# I-Ching_connection_board_v3_2020-09-12_0.net
KiCad netlist of a schematic drawn in EasyEDA
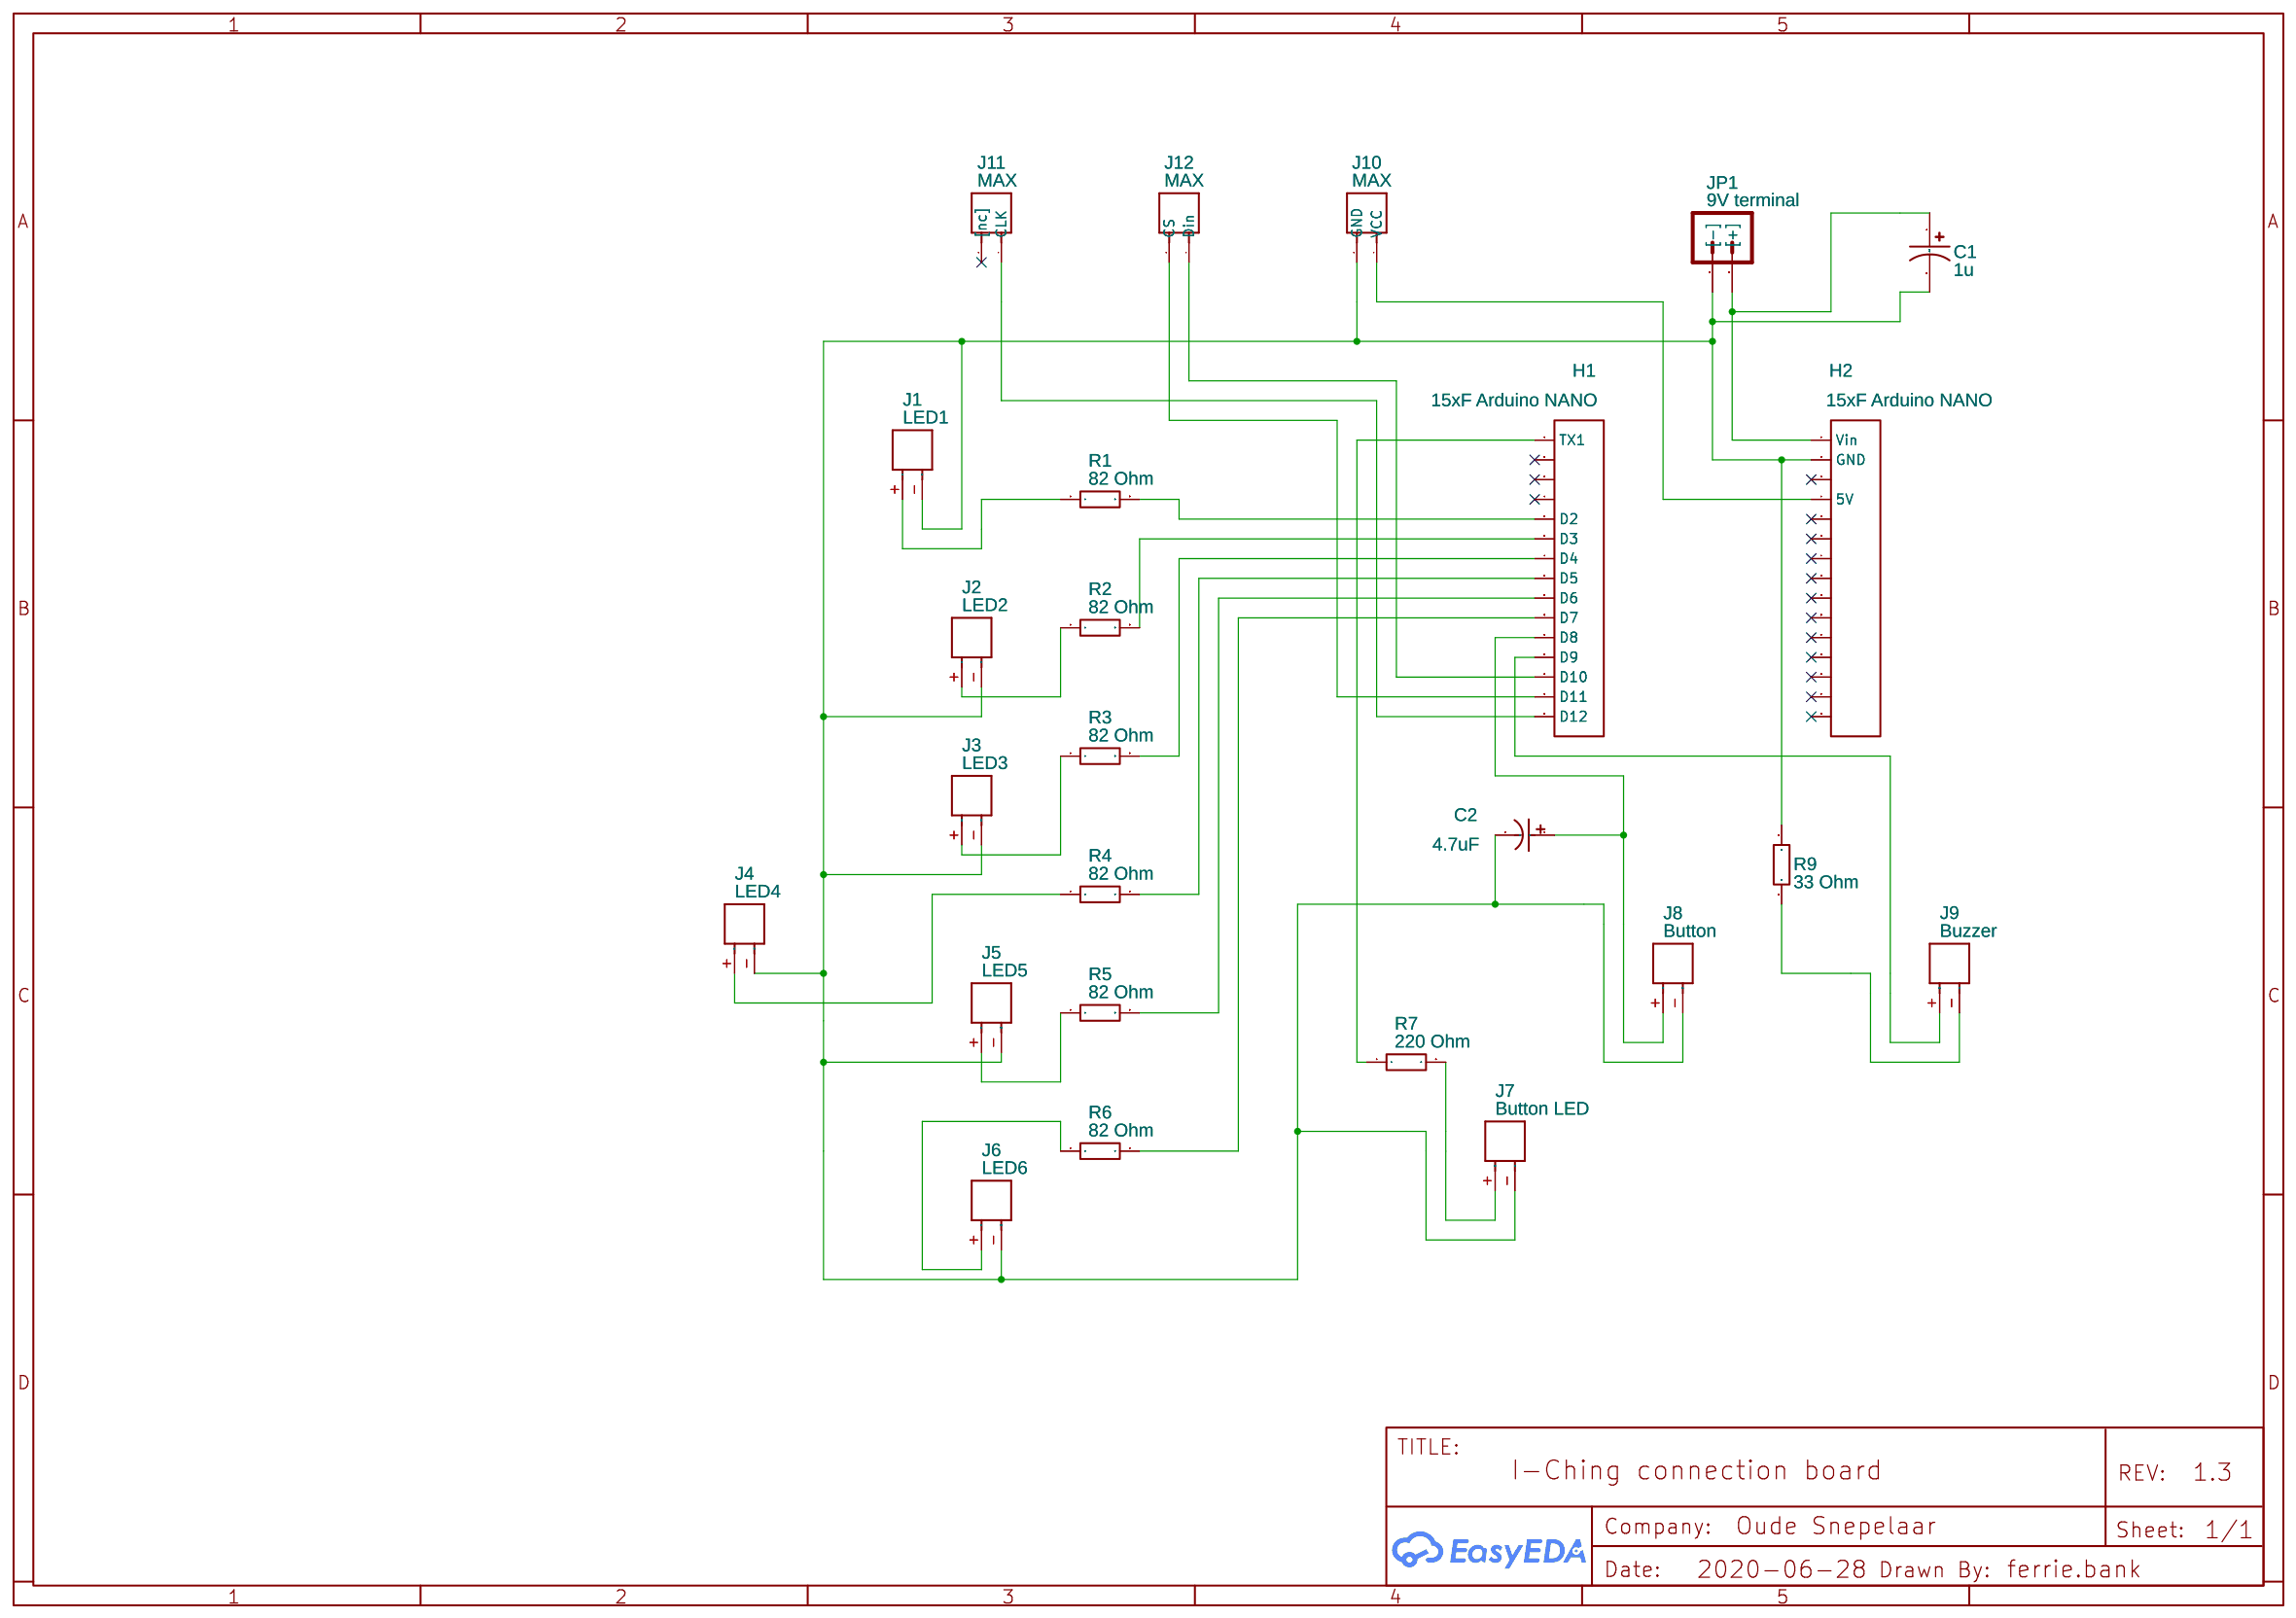
[diagram p0: schematic sheet]

(export (version "E")
  (design (tool "Eeschema 10.0.6"))
  (components
    (comp (ref "C1") (value "1u") (libsource (lib "") (part "CE_TH_D5.0×F2.0_US")))
    (comp (ref "C2")
      (value "4.7uF")
      (fields (field (name "BOM_Manufacturer Part") "0.1UF 50V") (field (name "BOM_Supplier Part") "C28061"))
      (libsource (lib "") (part "0.1UF 50V"))
    )
    (comp (ref "H1")
      (value "15xF Arduino NANO")
      (fields
        (field (name "BOM_Manufacturer Part") "220S-1*15P H=8.5MM Ytype Gold-plated")
        (field (name "BOM_Supplier Part") "C124408")
      )
      (libsource (lib "") (part "Header-Female-2.54_1x15_1"))
    )
    (comp (ref "H2")
      (value "15xF Arduino NANO")
      (fields
        (field (name "BOM_Manufacturer Part") "220S-1*15P H=8.5MM Ytype Gold-plated")
        (field (name "BOM_Supplier Part") "C124408")
      )
      (libsource (lib "") (part "Header-Female-2.54_1x15"))
    )
    (comp (ref "J1")
      (value "LED1")
      (fields (field (name "BOM_Manufacturer Part") "ZB2001-02"))
      (libsource (lib "") (part "ZB2001-02_1"))
    )
    (comp (ref "J2")
      (value "LED2")
      (fields (field (name "BOM_Manufacturer Part") "ZB2001-02"))
      (libsource (lib "") (part "ZB2001-02_1"))
    )
    (comp (ref "J3")
      (value "LED3")
      (fields (field (name "BOM_Manufacturer Part") "ZB2001-02"))
      (libsource (lib "") (part "ZB2001-02_1"))
    )
    (comp (ref "J4")
      (value "LED4")
      (fields (field (name "BOM_Manufacturer Part") "ZB2001-02"))
      (libsource (lib "") (part "ZB2001-02_1"))
    )
    (comp (ref "J5")
      (value "LED5")
      (fields (field (name "BOM_Manufacturer Part") "ZB2001-02"))
      (libsource (lib "") (part "ZB2001-02_1"))
    )
    (comp (ref "J6")
      (value "LED6")
      (fields (field (name "BOM_Manufacturer Part") "ZB2001-02"))
      (libsource (lib "") (part "ZB2001-02_1"))
    )
    (comp (ref "J7")
      (value "Button LED")
      (fields (field (name "BOM_Manufacturer Part") "ZB2001-02"))
      (libsource (lib "") (part "ZB2001-02_1"))
    )
    (comp (ref "J8")
      (value "Button")
      (fields (field (name "BOM_Manufacturer Part") "ZB2001-02"))
      (libsource (lib "") (part "ZB2001-02_1"))
    )
    (comp (ref "J9")
      (value "Buzzer")
      (fields (field (name "BOM_Manufacturer Part") "ZB2001-02"))
      (libsource (lib "") (part "ZB2001-02_1"))
    )
    (comp (ref "J10")
      (value "MAX")
      (fields (field (name "BOM_Manufacturer Part") "ZB2001-02"))
      (libsource (lib "") (part "ZB2001-02_3"))
    )
    (comp (ref "J11")
      (value "MAX")
      (fields (field (name "BOM_Manufacturer Part") "ZB2001-02"))
      (libsource (lib "") (part "ZB2001-02_2"))
    )
    (comp (ref "J12")
      (value "MAX")
      (fields (field (name "BOM_Manufacturer Part") "ZB2001-02"))
      (libsource (lib "") (part "ZB2001-02"))
    )
    (comp (ref "JP1") (value "9V terminal") (libsource (lib "") (part "Screw Terminal 2-Pin (5mm Pitch)")))
    (comp (ref "R1")
      (value "82 Ohm")
      (fields
        (field (name "BOM_Manufacturer Part") "MFR-25FTE52-300K")
        (field (name "BOM_Supplier Part") "C173001")
      )
      (libsource (lib "") (part "MFR-25FTE52-300K"))
    )
    (comp (ref "R2")
      (value "82 Ohm")
      (fields
        (field (name "BOM_Manufacturer Part") "MFR-25FTE52-300K")
        (field (name "BOM_Supplier Part") "C173001")
      )
      (libsource (lib "") (part "MFR-25FTE52-300K"))
    )
    (comp (ref "R3")
      (value "82 Ohm")
      (fields
        (field (name "BOM_Manufacturer Part") "MFR-25FTE52-300K")
        (field (name "BOM_Supplier Part") "C173001")
      )
      (libsource (lib "") (part "MFR-25FTE52-300K"))
    )
    (comp (ref "R4")
      (value "82 Ohm")
      (fields
        (field (name "BOM_Manufacturer Part") "MFR-25FTE52-300K")
        (field (name "BOM_Supplier Part") "C173001")
      )
      (libsource (lib "") (part "MFR-25FTE52-300K"))
    )
    (comp (ref "R5")
      (value "82 Ohm")
      (fields
        (field (name "BOM_Manufacturer Part") "MFR-25FTE52-300K")
        (field (name "BOM_Supplier Part") "C173001")
      )
      (libsource (lib "") (part "MFR-25FTE52-300K"))
    )
    (comp (ref "R6")
      (value "82 Ohm")
      (fields
        (field (name "BOM_Manufacturer Part") "MFR-25FTE52-300K")
        (field (name "BOM_Supplier Part") "C173001")
      )
      (libsource (lib "") (part "MFR-25FTE52-300K"))
    )
    (comp (ref "R7")
      (value "220 Ohm")
      (fields
        (field (name "BOM_Manufacturer Part") "MFR-25FTE52-300K")
        (field (name "BOM_Supplier Part") "C173001")
      )
      (libsource (lib "") (part "MFR-25FTE52-300K"))
    )
    (comp (ref "R9")
      (value "33 Ohm")
      (fields
        (field (name "BOM_Manufacturer Part") "MFR-25FTE52-300K")
        (field (name "BOM_Supplier Part") "C173001")
      )
      (libsource (lib "") (part "MFR-25FTE52-300K_1"))
    )
  )
  (nets
    (net (code "1") (name "Net-(H1-D2)") (class "Default")
      (node (ref "H1") (pin "5") (pinfunction "D2_5") (pintype "unspecified"))
      (node (ref "R1") (pin "2") (pinfunction "2_2") (pintype "unspecified"))
    )
    (net (code "2") (name "Net-(H1-D3)") (class "Default")
      (node (ref "H1") (pin "6") (pinfunction "D3_6") (pintype "unspecified"))
      (node (ref "R2") (pin "2") (pinfunction "2_2") (pintype "unspecified"))
    )
    (net (code "3") (name "Net-(H1-D4)") (class "Default")
      (node (ref "H1") (pin "7") (pinfunction "D4_7") (pintype "unspecified"))
      (node (ref "R3") (pin "2") (pinfunction "2_2") (pintype "unspecified"))
    )
    (net (code "4") (name "Net-(H1-D5)") (class "Default")
      (node (ref "H1") (pin "8") (pinfunction "D5_8") (pintype "unspecified"))
      (node (ref "R4") (pin "2") (pinfunction "2_2") (pintype "unspecified"))
    )
    (net (code "5") (name "Net-(H1-D6)") (class "Default")
      (node (ref "H1") (pin "9") (pinfunction "D6_9") (pintype "unspecified"))
      (node (ref "R5") (pin "2") (pinfunction "2_2") (pintype "unspecified"))
    )
    (net (code "6") (name "Net-(H1-D7)") (class "Default")
      (node (ref "H1") (pin "10") (pinfunction "D7_10") (pintype "unspecified"))
      (node (ref "R6") (pin "2") (pinfunction "2_2") (pintype "unspecified"))
    )
    (net (code "7") (name "Net-(H1-D8)") (class "Default")
      (node (ref "C2") (pin "1") (pinfunction "1_1") (pintype "input"))
      (node (ref "H1") (pin "11") (pinfunction "D8_11") (pintype "unspecified"))
      (node (ref "J8") (pin "+") (pinfunction "P$1_+") (pintype "unspecified"))
    )
    (net (code "8") (name "Net-(H1-D9)") (class "Default")
      (node (ref "H1") (pin "12") (pinfunction "D9_12") (pintype "unspecified"))
      (node (ref "J9") (pin "+") (pinfunction "P$1_+") (pintype "unspecified"))
    )
    (net (code "9") (name "Net-(H1-D10)") (class "Default")
      (node (ref "H1") (pin "13") (pinfunction "D10_13") (pintype "unspecified"))
      (node (ref "J12") (pin "-") (pinfunction "Din_-") (pintype "unspecified"))
    )
    (net (code "10") (name "Net-(H1-D11)") (class "Default")
      (node (ref "H1") (pin "14") (pinfunction "D11_14") (pintype "unspecified"))
      (node (ref "J12") (pin "+") (pinfunction "CS_+") (pintype "unspecified"))
    )
    (net (code "11") (name "Net-(H1-D12)") (class "Default")
      (node (ref "H1") (pin "15") (pinfunction "D12_15") (pintype "unspecified"))
      (node (ref "J11") (pin "-") (pinfunction "CLK_-") (pintype "unspecified"))
    )
    (net (code "12") (name "Net-(H1-TX1)") (class "Default")
      (node (ref "H1") (pin "1") (pinfunction "TX1_1") (pintype "unspecified"))
      (node (ref "R7") (pin "1") (pinfunction "1_1") (pintype "unspecified"))
    )
    (net (code "13") (name "Net-(H2-5V)") (class "Default")
      (node (ref "H2") (pin "4") (pinfunction "5V_4") (pintype "unspecified"))
      (node (ref "J10") (pin "-") (pinfunction "VCC_-") (pintype "unspecified"))
    )
    (net (code "14") (name "Net-(H2-GND)") (class "Default")
      (node (ref "C1") (pin "2") (pinfunction "2_2") (pintype "unspecified"))
      (node (ref "C2") (pin "2") (pinfunction "2_2") (pintype "input"))
      (node (ref "H2") (pin "2") (pinfunction "GND_2") (pintype "unspecified"))
      (node (ref "J1") (pin "-") (pinfunction "P$2_-") (pintype "unspecified"))
      (node (ref "J10") (pin "+") (pinfunction "GND_+") (pintype "unspecified"))
      (node (ref "J2") (pin "-") (pinfunction "P$2_-") (pintype "unspecified"))
      (node (ref "J3") (pin "-") (pinfunction "P$2_-") (pintype "unspecified"))
      (node (ref "J4") (pin "-") (pinfunction "P$2_-") (pintype "unspecified"))
      (node (ref "J5") (pin "-") (pinfunction "P$2_-") (pintype "unspecified"))
      (node (ref "J6") (pin "-") (pinfunction "P$2_-") (pintype "unspecified"))
      (node (ref "J7") (pin "-") (pinfunction "P$2_-") (pintype "unspecified"))
      (node (ref "J8") (pin "-") (pinfunction "P$2_-") (pintype "unspecified"))
      (node (ref "JP1") (pin "1") (pinfunction "[-]_1") (pintype "unspecified"))
      (node (ref "R9") (pin "1") (pinfunction "1_1") (pintype "unspecified"))
    )
    (net (code "15") (name "Net-(H2-Vin)") (class "Default")
      (node (ref "C1") (pin "1") (pinfunction "1_1") (pintype "unspecified"))
      (node (ref "H2") (pin "1") (pinfunction "Vin_1") (pintype "unspecified"))
      (node (ref "JP1") (pin "2") (pinfunction "[+]_2") (pintype "unspecified"))
    )
    (net (code "16") (name "Net-(J1-P$1)") (class "Default")
      (node (ref "J1") (pin "+") (pinfunction "P$1_+") (pintype "unspecified"))
      (node (ref "R1") (pin "1") (pinfunction "1_1") (pintype "unspecified"))
    )
    (net (code "17") (name "Net-(J2-P$1)") (class "Default")
      (node (ref "J2") (pin "+") (pinfunction "P$1_+") (pintype "unspecified"))
      (node (ref "R2") (pin "1") (pinfunction "1_1") (pintype "unspecified"))
    )
    (net (code "18") (name "Net-(J3-P$1)") (class "Default")
      (node (ref "J3") (pin "+") (pinfunction "P$1_+") (pintype "unspecified"))
      (node (ref "R3") (pin "1") (pinfunction "1_1") (pintype "unspecified"))
    )
    (net (code "19") (name "Net-(J4-P$1)") (class "Default")
      (node (ref "J4") (pin "+") (pinfunction "P$1_+") (pintype "unspecified"))
      (node (ref "R4") (pin "1") (pinfunction "1_1") (pintype "unspecified"))
    )
    (net (code "20") (name "Net-(J5-P$1)") (class "Default")
      (node (ref "J5") (pin "+") (pinfunction "P$1_+") (pintype "unspecified"))
      (node (ref "R5") (pin "1") (pinfunction "1_1") (pintype "unspecified"))
    )
    (net (code "21") (name "Net-(J6-P$1)") (class "Default")
      (node (ref "J6") (pin "+") (pinfunction "P$1_+") (pintype "unspecified"))
      (node (ref "R6") (pin "1") (pinfunction "1_1") (pintype "unspecified"))
    )
    (net (code "22") (name "Net-(J7-P$1)") (class "Default")
      (node (ref "J7") (pin "+") (pinfunction "P$1_+") (pintype "unspecified"))
      (node (ref "R7") (pin "2") (pinfunction "2_2") (pintype "unspecified"))
    )
    (net (code "23") (name "Net-(J9-P$2)") (class "Default")
      (node (ref "J9") (pin "-") (pinfunction "P$2_-") (pintype "unspecified"))
      (node (ref "R9") (pin "2") (pinfunction "2_2") (pintype "unspecified"))
    )
    (net (code "24") (name "unconnected-(H1-Pad2)") (class "Default")
      (node (ref "H1") (pin "2") (pintype "unspecified+no_connect"))
    )
    (net (code "25") (name "unconnected-(H1-Pad3)") (class "Default")
      (node (ref "H1") (pin "3") (pintype "unspecified+no_connect"))
    )
    (net (code "26") (name "unconnected-(H1-Pad4)") (class "Default")
      (node (ref "H1") (pin "4") (pintype "unspecified+no_connect"))
    )
    (net (code "27") (name "unconnected-(H2-Pad3)") (class "Default")
      (node (ref "H2") (pin "3") (pintype "unspecified+no_connect"))
    )
    (net (code "28") (name "unconnected-(H2-Pad5)") (class "Default")
      (node (ref "H2") (pin "5") (pintype "unspecified+no_connect"))
    )
    (net (code "29") (name "unconnected-(H2-Pad6)") (class "Default")
      (node (ref "H2") (pin "6") (pintype "unspecified+no_connect"))
    )
    (net (code "30") (name "unconnected-(H2-Pad7)") (class "Default")
      (node (ref "H2") (pin "7") (pintype "unspecified+no_connect"))
    )
    (net (code "31") (name "unconnected-(H2-Pad8)") (class "Default")
      (node (ref "H2") (pin "8") (pintype "unspecified+no_connect"))
    )
    (net (code "32") (name "unconnected-(H2-Pad9)") (class "Default")
      (node (ref "H2") (pin "9") (pintype "unspecified+no_connect"))
    )
    (net (code "33") (name "unconnected-(H2-Pad10)") (class "Default")
      (node (ref "H2") (pin "10") (pintype "unspecified+no_connect"))
    )
    (net (code "34") (name "unconnected-(H2-Pad11)") (class "Default")
      (node (ref "H2") (pin "11") (pintype "unspecified+no_connect"))
    )
    (net (code "35") (name "unconnected-(H2-Pad12)") (class "Default")
      (node (ref "H2") (pin "12") (pintype "unspecified+no_connect"))
    )
    (net (code "36") (name "unconnected-(H2-Pad13)") (class "Default")
      (node (ref "H2") (pin "13") (pintype "unspecified+no_connect"))
    )
    (net (code "37") (name "unconnected-(H2-Pad14)") (class "Default")
      (node (ref "H2") (pin "14") (pintype "unspecified+no_connect"))
    )
    (net (code "38") (name "unconnected-(H2-Pad15)") (class "Default")
      (node (ref "H2") (pin "15") (pintype "unspecified+no_connect"))
    )
    (net (code "39") (name "unconnected-(J11-[nc]-Pad+)") (class "Default")
      (node (ref "J11") (pin "+") (pinfunction "[nc]_+") (pintype "unspecified+no_connect"))
    )
  )
)
